# THERMO_SENSOR.net
KiCad netlist of a schematic drawn in Altium Designer
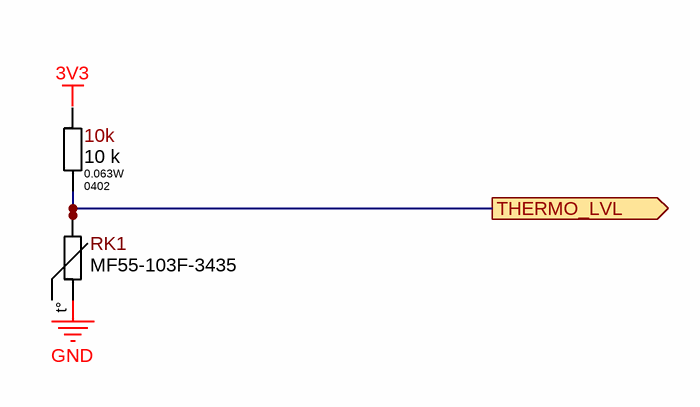
[diagram p0: THERMO_SENSOR.SchDoc]

(export (version "E")
  (design (tool "Eeschema 10.0.6"))
  (components
    (comp (ref "10k")
      (value "10 k")
      (footprint "R0402")
      (description "RES SMD 10 k OHM  ±1% 1/16W 0402")
      (fields
        (field (name "POWER RATING") "0.063W")
        (field (name "PACKAGE/CASE") "0402")
        (field (name "PART NUMBER") "10 k  R0402")
        (field (name "TOLERANCE") "±1%")
      )
      (libsource (lib "Database") (part "R0402"))
    )
    (comp (ref "RK1")
      (value "MF55-103F-3435")
      (footprint "MF55-103F-3435")
      (description "10 kOhm ±1% Thermistors, Radial Leaded, 3435 K B Parameter, 28.5x3.6mm, Max 0.6mm Thickness")
      (fields
        (field (name "PART NUMBER") "MF55-103F-3435")
        (field (name "MANUFACTURER") "Dongguan Tianrui Electronics Co")
      )
      (libsource (lib "AjaxLibrary") (part "NTC-Thermistor"))
    )
  )
  (nets
    (net (code "1") (name "/THERMO_LVL") (class "Default")
      (node (ref "10k") (pin "1") (pinfunction "1_1") (pintype "passive"))
      (node (ref "RK1") (pin "1") (pintype "passive"))
    )
    (net (code "3") (name "GND") (class "Default") (node (ref "RK1") (pin "2") (pintype "passive")))
    (net (code "4") (name "unconnected-(10k-Pad2)") (class "Default")
      (node (ref "10k") (pin "2") (pinfunction "2_2") (pintype "passive"))
    )
  )
)
